# MULTIB.net
KiCad netlist of a schematic drawn in Altium Designer
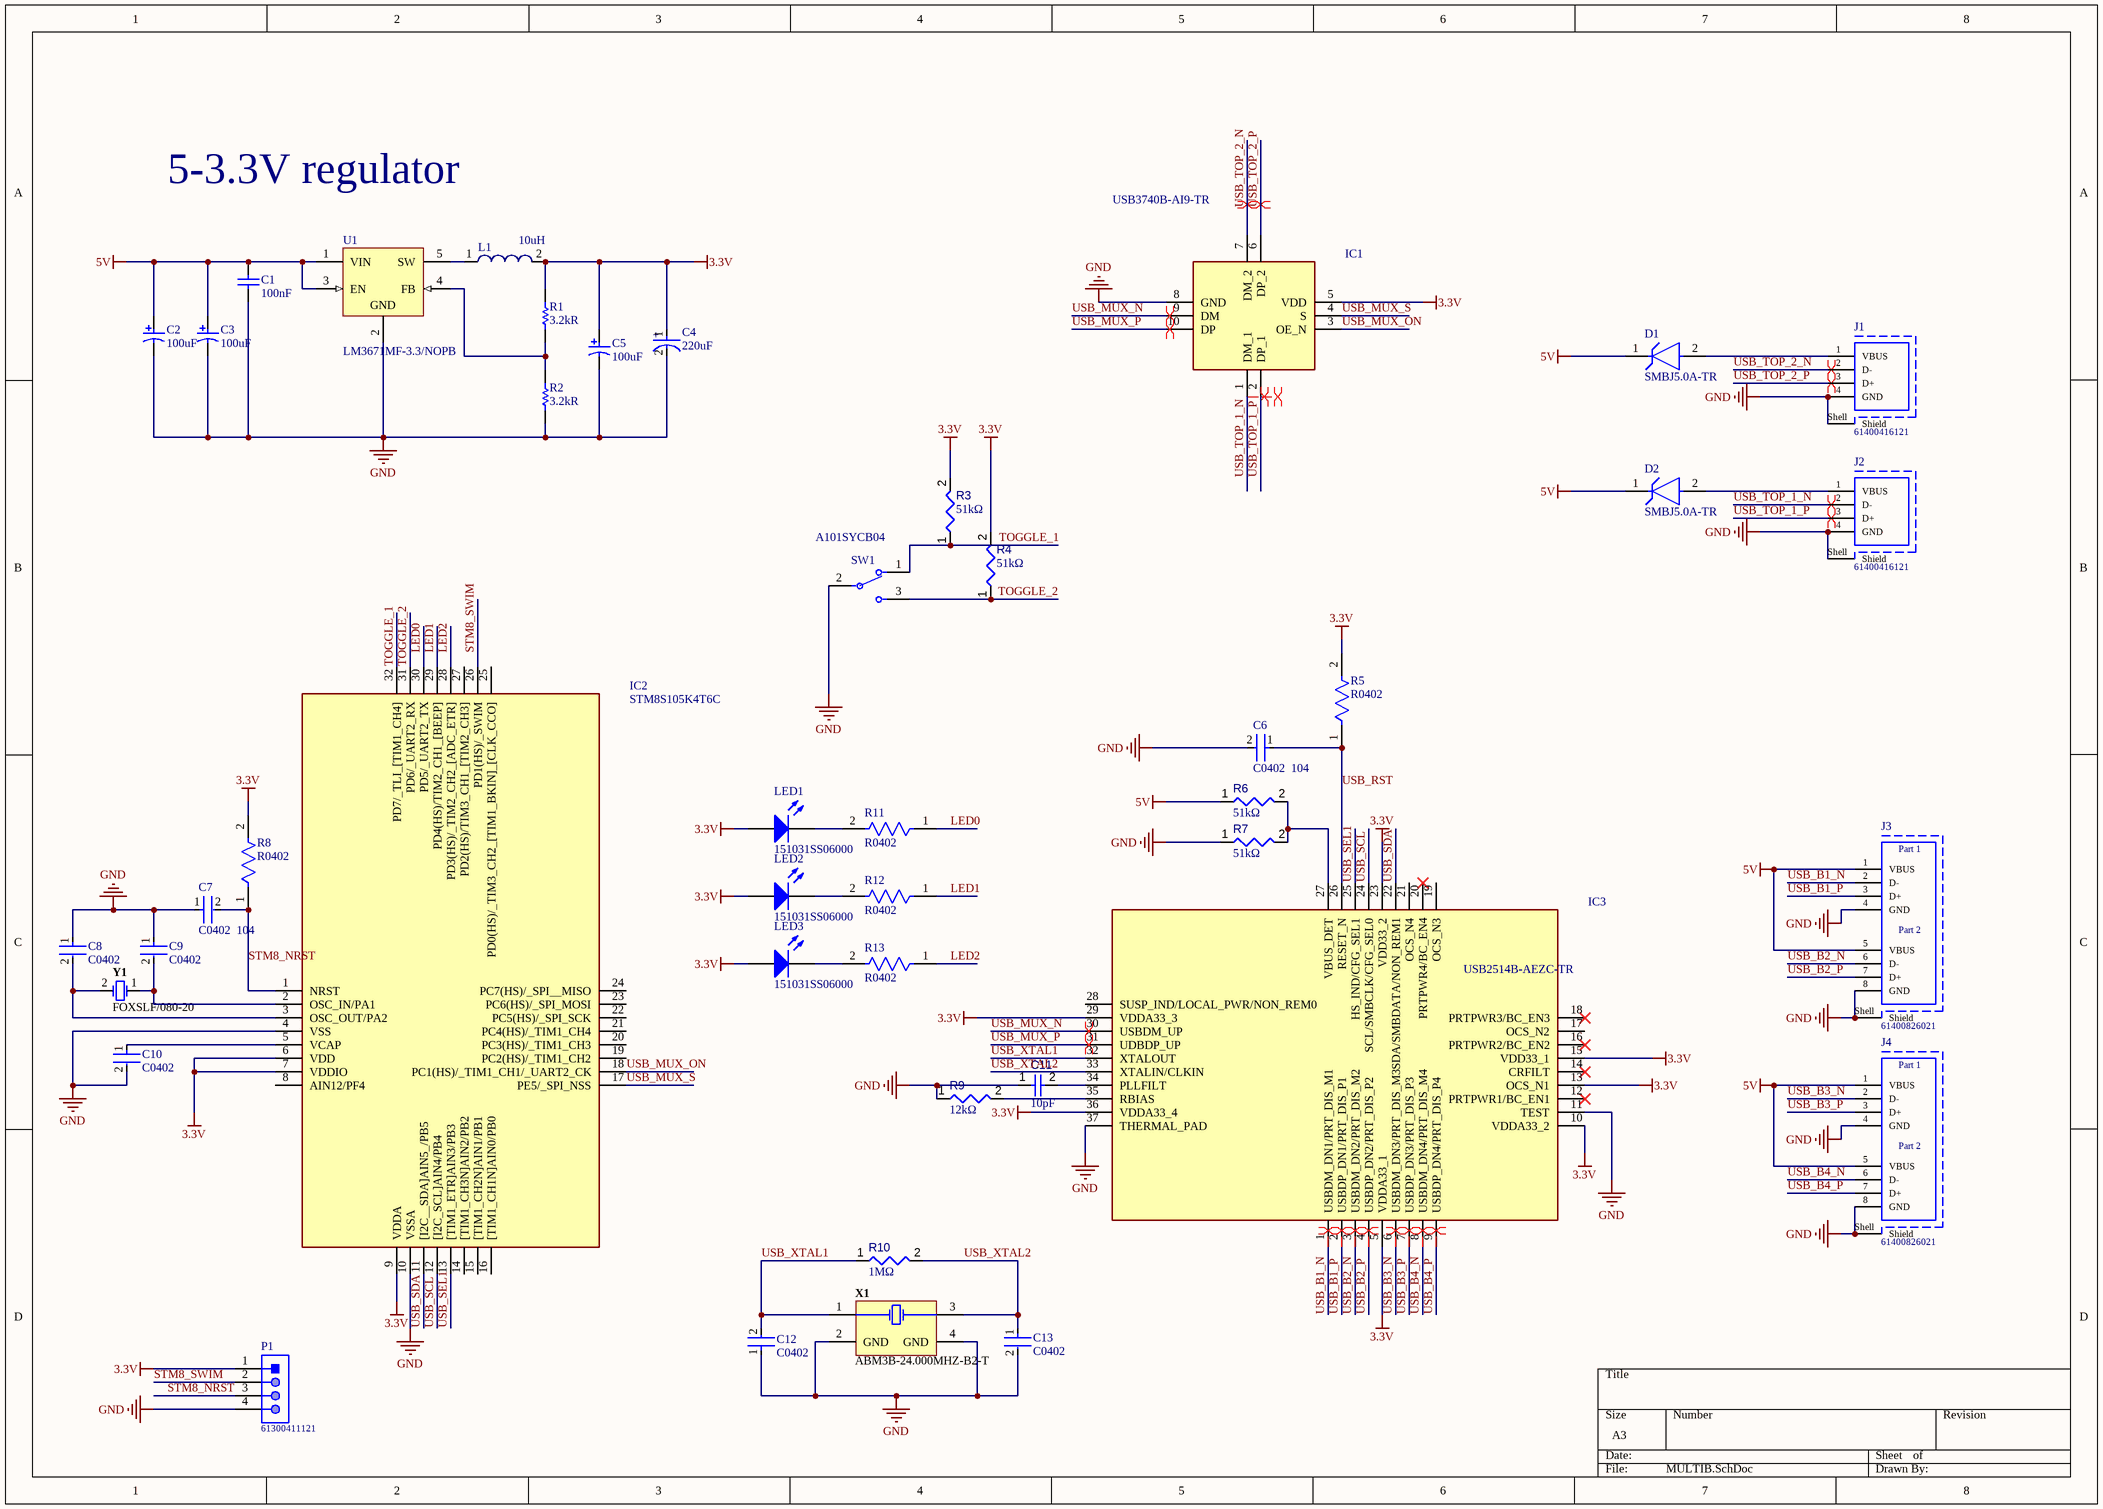
[diagram p0: MULTIB.SchDoc]

(export (version "E")
  (design (tool "Eeschema 10.0.6"))
  (components
    (comp (ref "C1")
      (value "100nF")
      (footprint "CAPC1608X90X35ML10T15")
      (description "Chip Capacitor, 22 pF, +/- 5%, 50 V, -55 to 125 degC, 0603 (1608 Metric), RoHS, Tape and Reel")
      (fields (field (name "MANUFACTURER") "Murata"))
      (libsource (lib "Altium Content Vault") (part "CAP-NP-2"))
    )
    (comp (ref "C2")
      (value "100uF")
      (footprint "CAPPR65-350-1150X800X1250")
      (description "Aluminum Electrolytic Capacitor, 100 uF, +/- 20%, 50 V, -40 to 85 degC, 2-Pin THD, RoHS, Bulk")
      (fields (field (name "MANUFACTURER") "Panasonic") (field (name "VOLTAGE") "50V"))
      (libsource (lib "Altium Content Vault") (part "CAP-P-2"))
    )
    (comp (ref "C3")
      (value "100uF")
      (footprint "CAPPR65-350-1150X800X1250")
      (description "Aluminum Electrolytic Capacitor, 100 uF, +/- 20%, 50 V, -40 to 85 degC, 2-Pin THD, RoHS, Bulk")
      (fields (field (name "MANUFACTURER") "Panasonic") (field (name "VOLTAGE") "50V"))
      (libsource (lib "Altium Content Vault") (part "CAP-P-2"))
    )
    (comp (ref "C4")
      (value "220uF")
      (footprint "FP-EEU-FC1V221L-MFG")
      (description "CAP ALUM 220UF 20% 35V RADIAL")
      (fields
        (field (name "OCTOPART") "https://octopart.com/eeu-fc1v221l-panasonic-39478519")
        (field (name "MANUFACTURER") "Panasonic Electronic Components")
      )
      (libsource (lib "Altium Content Vault") (part "385ce6c70a3ab0aa1e866f00bd8ed49"))
    )
    (comp (ref "C5")
      (value "100uF")
      (footprint "CAPPR65-350-1150X800X1250")
      (description "Aluminum Electrolytic Capacitor, 100 uF, +/- 20%, 50 V, -40 to 85 degC, 2-Pin THD, RoHS, Bulk")
      (fields (field (name "MANUFACTURER") "Panasonic") (field (name "VOLTAGE") "50V"))
      (libsource (lib "Altium Content Vault") (part "CAP-P-2"))
    )
    (comp (ref "C6")
      (value "C0402  104")
      (footprint "FP-C0402-BB-MFG")
      (description "CAP CER 0.1UF 10V X5R 0402")
      (fields (field (name "MANUFACTURER") "Kemet") (field (name "TOLERANCE") "0.1"))
      (libsource (lib "Altium Content Vault") (part "b4654b650e69147ec39a6b967a45e02"))
    )
    (comp (ref "C7")
      (value "C0402  104")
      (footprint "FP-C0402-BB-MFG")
      (description "CAP CER 0.1UF 10V X5R 0402")
      (fields (field (name "MANUFACTURER") "Kemet") (field (name "TOLERANCE") "0.1"))
      (libsource (lib "Altium Content Vault") (part "b4654b650e69147ec39a6b967a45e02"))
    )
    (comp (ref "C8")
      (value "C0402")
      (footprint "FP-C0402-BB-MFG")
      (description "CAP CER 0.1UF 10V X5R 0402")
      (fields (field (name "MANUFACTURER") "Kemet") (field (name "TOLERANCE") "0.1"))
      (libsource (lib "Altium Content Vault") (part "b4654b650e69147ec39a6b967a45e02"))
    )
    (comp (ref "C9")
      (value "C0402")
      (footprint "FP-C0402-BB-MFG")
      (description "CAP CER 0.1UF 10V X5R 0402")
      (fields (field (name "MANUFACTURER") "Kemet") (field (name "TOLERANCE") "0.1"))
      (libsource (lib "Altium Content Vault") (part "b4654b650e69147ec39a6b967a45e02"))
    )
    (comp (ref "C10")
      (value "C0402")
      (footprint "FP-C0402-BB-MFG")
      (description "CAP CER 0.1UF 10V X5R 0402")
      (fields (field (name "MANUFACTURER") "Kemet") (field (name "TOLERANCE") "0.1"))
      (libsource (lib "Altium Content Vault") (part "b4654b650e69147ec39a6b967a45e02"))
    )
    (comp (ref "C11")
      (value "10pF")
      (footprint "CAPC1608X90X40ML10T20")
      (description "Chip Capacitor, 10 pF, +/- 5%, 50 V, 0603 (1608 Metric)")
      (fields (field (name "TOLERANCE") "5%") (field (name "Comment") "Capacitor 10 pF +/- 5% 50 V 0603"))
      (libsource (lib "Jacky Yuen") (part "CAP-NP-2"))
    )
    (comp (ref "C12")
      (value "C0402")
      (footprint "FP-C0402-BB-MFG")
      (description "CAP CER 0.1UF 10V X5R 0402")
      (fields (field (name "MANUFACTURER") "Kemet") (field (name "TOLERANCE") "0.1"))
      (libsource (lib "Altium Content Vault") (part "b4654b650e69147ec39a6b967a45e02"))
    )
    (comp (ref "C13")
      (value "C0402")
      (footprint "FP-C0402-BB-MFG")
      (description "CAP CER 0.1UF 10V X5R 0402")
      (fields (field (name "MANUFACTURER") "Kemet") (field (name "TOLERANCE") "0.1"))
      (libsource (lib "Altium Content Vault") (part "b4654b650e69147ec39a6b967a45e02"))
    )
    (comp (ref "D1")
      (value "SMBJ5.0A-TR")
      (footprint "FP-SMB-MFG")
      (description "TVS DIODE 5V 13.4V SMB")
      (fields
        (field (name "MANUFACTURER") "STMicroelectronics")
        (field (name "OCTOPART") "https://octopart.com/smbj5.0a-tr-stmicroelectronics-347079")
      )
      (libsource (lib "Altium Content Vault") (part "7ddec9f632b8482e96f7745d0fbdf39"))
    )
    (comp (ref "D2")
      (value "SMBJ5.0A-TR")
      (footprint "FP-SMB-MFG")
      (description "TVS DIODE 5V 13.4V SMB")
      (fields
        (field (name "MANUFACTURER") "STMicroelectronics")
        (field (name "OCTOPART") "https://octopart.com/smbj5.0a-tr-stmicroelectronics-347079")
      )
      (libsource (lib "Altium Content Vault") (part "7ddec9f632b8482e96f7745d0fbdf39"))
    )
    (comp (ref "IC1")
      (value "USB3740B-AI9-TR")
      (footprint "SamacSys:USB3740BAI9TR")
      (description "Integrated Circuit")
      (fields (field (name "MOUSER PART NUMBER") "886-USB3740B-AI9-TR"))
      (libsource (lib "*") (part "USB3740B-AI9-TR"))
    )
    (comp (ref "IC2")
      (value "STM8S105K4T6C")
      (footprint "SamacSys:QFP80P900X900X160-32N")
      (description "Integrated Circuit")
      (fields (field (name "MOUSER PART NUMBER") "511-STM8S105K4T6C"))
      (libsource (lib "*") (part "STM8S105K4T6C"))
    )
    (comp (ref "IC3")
      (value "USB2514B-AEZC-TR")
      (footprint "SamacSys:QFN50P600X600X100-37N-D")
      (description "Integrated Circuit")
      (fields (field (name "MOUSER PART NUMBER") "886-USB2514B-AEZC-TR"))
      (libsource (lib "*") (part "USB2514B-AEZC-TR"))
    )
    (comp (ref "J1")
      (value "61400416121")
      (footprint "61400416121")
      (description "USB 2.0 Type B Receptacle WR-COM, Horizontal, THT, with Pads and Pegs")
      (fields (field (name "MANUFACTURER") "Wurth Elektronik") (field (name "PUBLISHER") "WurthElektronik"))
      (libsource (lib "Altium Content Vault") (part "WE-USB-4-1SHLD"))
    )
    (comp (ref "J2")
      (value "61400416121")
      (footprint "61400416121")
      (description "USB 2.0 Type B Receptacle WR-COM, Horizontal, THT, with Pads and Pegs")
      (fields (field (name "MANUFACTURER") "Wurth Elektronik") (field (name "PUBLISHER") "WurthElektronik"))
      (libsource (lib "Altium Content Vault") (part "WE-USB-4-1SHLD"))
    )
    (comp (ref "J3")
      (value "61400826021")
      (footprint "61400826021")
      (description "USB 2.0 Type A Receptacle WR-COM, Stacked Horizontal, THT")
      (fields (field (name "MANUFACTURER") "Wurth Elektronik") (field (name "PUBLISHER") "WurthElektronik"))
      (libsource (lib "Altium Content Vault") (part "WE-USB-8-1SHLD"))
    )
    (comp (ref "J4")
      (value "61400826021")
      (footprint "61400826021")
      (description "USB 2.0 Type A Receptacle WR-COM, Stacked Horizontal, THT")
      (fields (field (name "MANUFACTURER") "Wurth Elektronik") (field (name "PUBLISHER") "WurthElektronik"))
      (libsource (lib "Altium Content Vault") (part "WE-USB-8-1SHLD"))
    )
    (comp (ref "L1")
      (value "10uH")
      (footprint "WE-SPC 4838")
      (description "SMD Shielded Power Inductor WE-SPC, L=10 µH")
      (fields (field (name "MANUFACTURER") "Wuerth Elektronik") (field (name "PARTNUMBER") "74408943100"))
      (libsource (lib "Altium Content Vault") (part "WE-IND-INDUCTOR-2"))
    )
    (comp (ref "LED1")
      (value "151031SS06000")
      (footprint "Type 3mm")
      (description "THT LED round mono-color color lens, WL-TMRW, Super Red")
      (fields (field (name "MANUFACTURER") "Wuerth Elektronik"))
      (libsource (lib "Altium Content Vault") (part "WE-LED_K1A2-2"))
    )
    (comp (ref "LED2")
      (value "151031SS06000")
      (footprint "Type 3mm")
      (description "THT LED round mono-color color lens, WL-TMRW, Super Red")
      (fields (field (name "MANUFACTURER") "Wuerth Elektronik"))
      (libsource (lib "Altium Content Vault") (part "WE-LED_K1A2-2"))
    )
    (comp (ref "LED3")
      (value "151031SS06000")
      (footprint "Type 3mm")
      (description "THT LED round mono-color color lens, WL-TMRW, Super Red")
      (fields (field (name "MANUFACTURER") "Wuerth Elektronik"))
      (libsource (lib "Altium Content Vault") (part "WE-LED_K1A2-2"))
    )
    (comp (ref "P1")
      (value "61300411121")
      (footprint "61300411121")
      (description "THT Vertical Pin Header WR-PHD, Pitch 2.54 mm, Single Row, 4 pins")
      (fields (field (name "MANUFACTURER") "Wurth Elektronik") (field (name "PUBLISHER") "WurthElektronik"))
      (libsource (lib "Altium Content Vault") (part "WE-CN-1P-M-R4"))
    )
    (comp (ref "R1")
      (value "3.2kR")
      (footprint "RESC1005X40X25LL05T05")
      (description "Chip Resistor, 4.7 KOhm, +/- 1%, 0.1 W, -55 to 155 degC, 0402 (1005 Metric), RoHS, Tape and Reel")
      (fields (field (name "TOLERANCE") "1%") (field (name "PARTNUMBER") "ERJ-2RKF4701X"))
      (libsource (lib "Altium Content Vault") (part "RES-2"))
    )
    (comp (ref "R2")
      (value "3.2kR")
      (footprint "RESC1005X40X25LL05T05")
      (description "Chip Resistor, 4.7 KOhm, +/- 1%, 0.1 W, -55 to 155 degC, 0402 (1005 Metric), RoHS, Tape and Reel")
      (fields (field (name "TOLERANCE") "1%") (field (name "PARTNUMBER") "ERJ-2RKF4701X"))
      (libsource (lib "Altium Content Vault") (part "RES-2"))
    )
    (comp (ref "R3")
      (value "51kΩ")
      (footprint "RESC0603(1608)_L")
      (description "120R 0.1W 5% 0603 (1608 Metric)  SMD")
      (fields (field (name "POWER") "0.1W") (field (name "TOLERANCE") "5%"))
      (libsource (lib "Jacky Yuen") (part "120R3J"))
    )
    (comp (ref "R4")
      (value "51kΩ")
      (footprint "RESC0603(1608)_L")
      (description "120R 0.1W 5% 0603 (1608 Metric)  SMD")
      (fields (field (name "POWER") "0.1W") (field (name "TOLERANCE") "5%"))
      (libsource (lib "Jacky Yuen") (part "120R3J"))
    )
    (comp (ref "R5")
      (value "R0402")
      (footprint "FP-CRCW0402-e3-IPC_C")
      (description "RES Thick Film, 32.4kΩ, 1%, 0.063W, 100ppm/°C, 0402")
      (fields (field (name "TOLERANCE") "1%"))
      (libsource (lib "Altium Content Vault") (part "1029c3af85768c4190bb7ad29bc67b5"))
    )
    (comp (ref "R6")
      (value "51kΩ")
      (footprint "RESC0603(1608)_L")
      (description "120R 0.1W 5% 0603 (1608 Metric)  SMD")
      (fields (field (name "POWER") "0.1W") (field (name "TOLERANCE") "5%"))
      (libsource (lib "Jacky Yuen") (part "120R3J"))
    )
    (comp (ref "R7")
      (value "51kΩ")
      (footprint "RESC0603(1608)_L")
      (description "120R 0.1W 5% 0603 (1608 Metric)  SMD")
      (fields (field (name "POWER") "0.1W") (field (name "TOLERANCE") "5%"))
      (libsource (lib "Jacky Yuen") (part "120R3J"))
    )
    (comp (ref "R8")
      (value "R0402")
      (footprint "FP-CRCW0402-e3-IPC_C")
      (description "RES Thick Film, 32.4kΩ, 1%, 0.063W, 100ppm/°C, 0402")
      (fields (field (name "TOLERANCE") "1%"))
      (libsource (lib "Altium Content Vault") (part "1029c3af85768c4190bb7ad29bc67b5"))
    )
    (comp (ref "R9")
      (value "12kΩ")
      (footprint "RESC0603(1608)_L")
      (description "120R 0.1W 5% 0603 (1608 Metric)  SMD")
      (fields (field (name "POWER") "0.1W") (field (name "TOLERANCE") "5%"))
      (libsource (lib "Jacky Yuen") (part "120R3J"))
    )
    (comp (ref "R10")
      (value "1MΩ")
      (footprint "RESC0603(1608)_L")
      (description "120R 0.1W 5% 0603 (1608 Metric)  SMD")
      (fields (field (name "POWER") "0.1W") (field (name "TOLERANCE") "5%"))
      (libsource (lib "Jacky Yuen") (part "120R3J"))
    )
    (comp (ref "R11")
      (value "R0402")
      (footprint "FP-CRCW0402-e3-IPC_C")
      (description "RES Thick Film, 32.4kΩ, 1%, 0.063W, 100ppm/°C, 0402")
      (fields (field (name "TOLERANCE") "1%"))
      (libsource (lib "Altium Content Vault") (part "1029c3af85768c4190bb7ad29bc67b5"))
    )
    (comp (ref "R12")
      (value "R0402")
      (footprint "FP-CRCW0402-e3-IPC_C")
      (description "RES Thick Film, 32.4kΩ, 1%, 0.063W, 100ppm/°C, 0402")
      (fields (field (name "TOLERANCE") "1%"))
      (libsource (lib "Altium Content Vault") (part "1029c3af85768c4190bb7ad29bc67b5"))
    )
    (comp (ref "R13")
      (value "R0402")
      (footprint "FP-CRCW0402-e3-IPC_C")
      (description "RES Thick Film, 32.4kΩ, 1%, 0.063W, 100ppm/°C, 0402")
      (fields (field (name "TOLERANCE") "1%"))
      (libsource (lib "Altium Content Vault") (part "1029c3af85768c4190bb7ad29bc67b5"))
    )
    (comp (ref "SW1")
      (value "A101SYCB04")
      (footprint "FP-A101SYCB04-MFG")
      (description "SWITCH TOGGLE SPDT 0.4VA 20V")
      (libsource (lib "Altium Content Vault") (part "52c419afdc2a387c7d548259a9aeefb"))
    )
    (comp (ref "U1")
      (value "LM3671MF-3.3/NOPB")
      (footprint "DBV0005A_N")
      (description "2MHz, 600mA Step-Down DC-DC Converter, 5-pin SOT-23, Pb-Free")
      (fields (field (name "MANUFACTURER") "Texas Instruments"))
      (libsource (lib "Altium Content Vault") (part "PM-DCDC-LM3670-5"))
    )
    (comp (ref "X1")
      (value "ABM3B-24.000MHZ-B2-T")
      (footprint "ABRA-ABM3B-4_V")
      (description "Ceramic SMD Crystal, 24 MHz, +/- 20 ppm, 50 Ohm, -20 to 70 degC, 4-Pin SMD, RoHS, Tape and Reel")
      (libsource (lib "Altium Content Vault") (part "XTAL-1-3-4"))
    )
    (comp (ref "Y1")
      (value "FOXSLF/080-20")
      (footprint "FOX-FOXSLF080-20")
      (description "Resistance Weld Thru-Hole Crystal, 8 MHz, -20 to 70 degC, 2-Pin THD, RoHS, Bulk")
      (libsource (lib "Altium Content Vault") (part "XTAL-1-2-2"))
    )
  )
  (nets
    (net (code "1") (name "/LED0") (class "Default")
      (node (ref "IC2") (pin "30") (pinfunction "PD5/_UART2_TX_30") (pintype "passive"))
      (node (ref "R11") (pin "1") (pinfunction "1_1") (pintype "passive"))
    )
    (net (code "2") (name "/LED1") (class "Default")
      (node (ref "IC2") (pin "29") (pinfunction "PD4(HS)/TIM2_CH1_[BEEP]_29") (pintype "passive"))
      (node (ref "R12") (pin "1") (pinfunction "1_1") (pintype "passive"))
    )
    (net (code "3") (name "/LED2") (class "Default")
      (node (ref "IC2") (pin "28") (pinfunction "PD3(HS)/_TIM2_CH2_[ADC_ETR]_28") (pintype "passive"))
      (node (ref "R13") (pin "1") (pinfunction "1_1") (pintype "passive"))
    )
    (net (code "4") (name "/STM8_NRST") (class "Default")
      (node (ref "C7") (pin "2") (pinfunction "2_2") (pintype "passive"))
      (node (ref "IC2") (pin "1") (pinfunction "NRST_1") (pintype "passive"))
      (node (ref "P1") (pin "3") (pinfunction "3_3") (pintype "passive"))
      (node (ref "R8") (pin "1") (pinfunction "1_1") (pintype "passive"))
    )
    (net (code "5") (name "/STM8_SWIM") (class "Default")
      (node (ref "IC2") (pin "26") (pinfunction "PD1(HS)/_SWIM_26") (pintype "passive"))
      (node (ref "P1") (pin "2") (pinfunction "2_2") (pintype "passive"))
    )
    (net (code "6") (name "/TOGGLE_1") (class "Default")
      (node (ref "IC2") (pin "32") (pinfunction "PD7/_TLI_[TIM1_CH4]_32") (pintype "passive"))
      (node (ref "R3") (pin "1") (pinfunction "1_1") (pintype "passive"))
      (node (ref "SW1") (pin "1") (pinfunction "1_1") (pintype "passive"))
    )
    (net (code "7") (name "/TOGGLE_2") (class "Default")
      (node (ref "IC2") (pin "31") (pinfunction "PD6/_UART2_RX_31") (pintype "passive"))
      (node (ref "R4") (pin "1") (pinfunction "1_1") (pintype "passive"))
      (node (ref "SW1") (pin "3") (pinfunction "3_3") (pintype "passive"))
    )
    (net (code "8") (name "/USB_B1_N") (class "Default")
      (node (ref "IC3") (pin "1") (pinfunction "USBDM_DN1/PRT_DIS_M1_1") (pintype "passive"))
      (node (ref "J3") (pin "2") (pinfunction "D-_2") (pintype "passive"))
    )
    (net (code "9") (name "/USB_B1_P") (class "Default")
      (node (ref "IC3") (pin "2") (pinfunction "USBDP_DN1/PRT_DIS_P1_2") (pintype "passive"))
      (node (ref "J3") (pin "3") (pinfunction "D+_3") (pintype "passive"))
    )
    (net (code "10") (name "/USB_B2_N") (class "Default")
      (node (ref "IC3") (pin "3") (pinfunction "USBDM_DN2/PRT_DIS_M2_3") (pintype "passive"))
      (node (ref "J3") (pin "6") (pinfunction "D-_6") (pintype "passive"))
    )
    (net (code "11") (name "/USB_B2_P") (class "Default")
      (node (ref "IC3") (pin "4") (pinfunction "USBDP_DN2/PRT_DIS_P2_4") (pintype "passive"))
      (node (ref "J3") (pin "7") (pinfunction "D+_7") (pintype "passive"))
    )
    (net (code "12") (name "/USB_B3_N") (class "Default")
      (node (ref "IC3") (pin "6") (pinfunction "USBDM_DN3/PRT_DIS_M3_6") (pintype "passive"))
      (node (ref "J4") (pin "2") (pinfunction "D-_2") (pintype "passive"))
    )
    (net (code "13") (name "/USB_B3_P") (class "Default")
      (node (ref "IC3") (pin "7") (pinfunction "USBDP_DN3/PRT_DIS_P3_7") (pintype "passive"))
      (node (ref "J4") (pin "3") (pinfunction "D+_3") (pintype "passive"))
    )
    (net (code "14") (name "/USB_B4_N") (class "Default")
      (node (ref "IC3") (pin "8") (pinfunction "USBDM_DN4/PRT_DIS_M4_8") (pintype "passive"))
      (node (ref "J4") (pin "6") (pinfunction "D-_6") (pintype "passive"))
    )
    (net (code "15") (name "/USB_B4_P") (class "Default")
      (node (ref "IC3") (pin "9") (pinfunction "USBDP_DN4/PRT_DIS_P4_9") (pintype "passive"))
      (node (ref "J4") (pin "7") (pinfunction "D+_7") (pintype "passive"))
    )
    (net (code "16") (name "/USB_MUX_N") (class "Default")
      (node (ref "IC1") (pin "9") (pinfunction "DM_9") (pintype "passive"))
      (node (ref "IC3") (pin "30") (pinfunction "USBDM_UP_30") (pintype "passive"))
    )
    (net (code "17") (name "/USB_MUX_ON") (class "Default")
      (node (ref "IC1") (pin "3") (pinfunction "OE_N_3") (pintype "passive"))
      (node (ref "IC2") (pin "18") (pinfunction "PC1(HS)/_TIM1_CH1/_UART2_CK_18") (pintype "passive"))
    )
    (net (code "18") (name "/USB_MUX_P") (class "Default")
      (node (ref "IC1") (pin "10") (pinfunction "DP_10") (pintype "passive"))
      (node (ref "IC3") (pin "31") (pinfunction "UDBDP_UP_31") (pintype "passive"))
    )
    (net (code "19") (name "/USB_MUX_S") (class "Default")
      (node (ref "IC1") (pin "4") (pinfunction "S_4") (pintype "passive"))
      (node (ref "IC2") (pin "17") (pinfunction "PE5/_SPI_NSS_17") (pintype "passive"))
    )
    (net (code "20") (name "/USB_RST") (class "Default")
      (node (ref "C6") (pin "1") (pinfunction "1_1") (pintype "passive"))
      (node (ref "IC3") (pin "26") (pinfunction "RESET_N_26") (pintype "passive"))
      (node (ref "R5") (pin "1") (pinfunction "1_1") (pintype "passive"))
    )
    (net (code "21") (name "/USB_SCL") (class "Default")
      (node (ref "IC2") (pin "12") (pinfunction "[I2C_SCL]AIN4/PB4_12") (pintype "passive"))
      (node (ref "IC3") (pin "24") (pinfunction "SCL/SMBCLK/CFG_SEL0_24") (pintype "passive"))
    )
    (net (code "22") (name "/USB_SDA") (class "Default")
      (node (ref "IC2") (pin "11") (pinfunction "[I2C__SDA]AIN5_/PB5_11") (pintype "passive"))
      (node (ref "IC3") (pin "22") (pinfunction "SDA/SMBDATA/NON_REM1_22") (pintype "passive"))
    )
    (net (code "23") (name "/USB_SEL1") (class "Default")
      (node (ref "IC2") (pin "13") (pinfunction "[TIM1_ETR]AIN3/PB3_13") (pintype "passive"))
      (node (ref "IC3") (pin "25") (pinfunction "HS_IND/CFG_SEL1_25") (pintype "passive"))
    )
    (net (code "24") (name "/USB_TOP_1_N") (class "Default")
      (node (ref "IC1") (pin "1") (pinfunction "DM_1_1") (pintype "passive"))
      (node (ref "J2") (pin "2") (pinfunction "D-_2") (pintype "passive"))
    )
    (net (code "25") (name "/USB_TOP_1_P") (class "Default")
      (node (ref "IC1") (pin "2") (pinfunction "DP_1_2") (pintype "passive"))
      (node (ref "J2") (pin "3") (pinfunction "D+_3") (pintype "passive"))
    )
    (net (code "26") (name "/USB_TOP_2_N") (class "Default")
      (node (ref "IC1") (pin "7") (pinfunction "DM_2_7") (pintype "passive"))
      (node (ref "J1") (pin "2") (pinfunction "D-_2") (pintype "passive"))
    )
    (net (code "27") (name "/USB_TOP_2_P") (class "Default")
      (node (ref "IC1") (pin "6") (pinfunction "DP_2_6") (pintype "passive"))
      (node (ref "J1") (pin "3") (pinfunction "D+_3") (pintype "passive"))
    )
    (net (code "28") (name "/USB_XTAL1") (class "Default")
      (node (ref "C12") (pin "2") (pinfunction "2_2") (pintype "passive"))
      (node (ref "IC3") (pin "32") (pinfunction "XTALOUT_32") (pintype "passive"))
      (node (ref "R10") (pin "1") (pinfunction "1_1") (pintype "passive"))
      (node (ref "X1") (pin "1") (pinfunction "X1_1") (pintype "passive"))
    )
    (net (code "29") (name "/USB_XTAL2") (class "Default")
      (node (ref "C13") (pin "1") (pinfunction "1_1") (pintype "passive"))
      (node (ref "IC3") (pin "33") (pinfunction "XTALIN/CLKIN_33") (pintype "passive"))
      (node (ref "R10") (pin "2") (pinfunction "2_2") (pintype "passive"))
      (node (ref "X1") (pin "3") (pinfunction "X2_3") (pintype "passive"))
    )
    (net (code "30") (name "3.3V") (class "Default")
      (node (ref "C4") (pin "1") (pinfunction "C_1") (pintype "passive"))
      (node (ref "C5") (pin "1") (pinfunction "1_1") (pintype "passive"))
      (node (ref "IC1") (pin "5") (pinfunction "VDD_5") (pintype "passive"))
      (node (ref "IC2") (pin "6") (pinfunction "VDD_6") (pintype "passive"))
      (node (ref "IC2") (pin "7") (pinfunction "VDDIO_7") (pintype "passive"))
      (node (ref "IC2") (pin "9") (pinfunction "VDDA_9") (pintype "passive"))
      (node (ref "IC3") (pin "10") (pinfunction "VDDA33_2_10") (pintype "passive"))
      (node (ref "IC3") (pin "13") (pinfunction "OCS_N1_13") (pintype "passive"))
      (node (ref "IC3") (pin "15") (pinfunction "VDD33_1_15") (pintype "passive"))
      (node (ref "IC3") (pin "23") (pinfunction "VDD33_2_23") (pintype "passive"))
      (node (ref "IC3") (pin "29") (pinfunction "VDDA33_3_29") (pintype "passive"))
      (node (ref "IC3") (pin "36") (pinfunction "VDDA33_4_36") (pintype "passive"))
      (node (ref "IC3") (pin "5") (pinfunction "VDDA33_1_5") (pintype "passive"))
      (node (ref "L1") (pin "2") (pinfunction "2_2") (pintype "passive"))
      (node (ref "LED1") (pin "2") (pinfunction "A_2") (pintype "passive"))
      (node (ref "LED2") (pin "2") (pinfunction "A_2") (pintype "passive"))
      (node (ref "LED3") (pin "2") (pinfunction "A_2") (pintype "passive"))
      (node (ref "P1") (pin "1") (pinfunction "1_1") (pintype "passive"))
      (node (ref "R1") (pin "2") (pinfunction "2_2") (pintype "passive"))
      (node (ref "R3") (pin "2") (pinfunction "2_2") (pintype "passive"))
      (node (ref "R4") (pin "2") (pinfunction "2_2") (pintype "passive"))
      (node (ref "R5") (pin "2") (pinfunction "2_2") (pintype "passive"))
      (node (ref "R8") (pin "2") (pinfunction "2_2") (pintype "passive"))
    )
    (net (code "31") (name "5V") (class "Default")
      (node (ref "C1") (pin "2") (pinfunction "2_2") (pintype "passive"))
      (node (ref "C2") (pin "1") (pinfunction "1_1") (pintype "passive"))
      (node (ref "C3") (pin "1") (pinfunction "1_1") (pintype "passive"))
      (node (ref "D1") (pin "1") (pinfunction "K_1") (pintype "passive"))
      (node (ref "D2") (pin "1") (pinfunction "K_1") (pintype "passive"))
      (node (ref "J3") (pin "1") (pinfunction "VBUS_1") (pintype "passive"))
      (node (ref "J3") (pin "5") (pinfunction "VBUS_5") (pintype "passive"))
      (node (ref "J4") (pin "1") (pinfunction "VBUS_1") (pintype "passive"))
      (node (ref "J4") (pin "5") (pinfunction "VBUS_5") (pintype "passive"))
      (node (ref "R6") (pin "1") (pinfunction "1_1") (pintype "passive"))
      (node (ref "U1") (pin "1") (pinfunction "VIN_1") (pintype "power_in"))
      (node (ref "U1") (pin "3") (pinfunction "EN_3") (pintype "input"))
    )
    (net (code "32") (name "GND") (class "Default")
      (node (ref "C1") (pin "1") (pinfunction "1_1") (pintype "passive"))
      (node (ref "C10") (pin "2") (pinfunction "2_2") (pintype "passive"))
      (node (ref "C11") (pin "1") (pinfunction "1_1") (pintype "passive"))
      (node (ref "C12") (pin "1") (pinfunction "1_1") (pintype "passive"))
      (node (ref "C13") (pin "2") (pinfunction "2_2") (pintype "passive"))
      (node (ref "C2") (pin "2") (pinfunction "2_2") (pintype "passive"))
      (node (ref "C3") (pin "2") (pinfunction "2_2") (pintype "passive"))
      (node (ref "C4") (pin "2") (pinfunction "A_2") (pintype "passive"))
      (node (ref "C5") (pin "2") (pinfunction "2_2") (pintype "passive"))
      (node (ref "C6") (pin "2") (pinfunction "2_2") (pintype "passive"))
      (node (ref "C7") (pin "1") (pinfunction "1_1") (pintype "passive"))
      (node (ref "C8") (pin "1") (pinfunction "1_1") (pintype "passive"))
      (node (ref "C9") (pin "1") (pinfunction "1_1") (pintype "passive"))
      (node (ref "IC1") (pin "8") (pinfunction "GND_8") (pintype "passive"))
      (node (ref "IC2") (pin "10") (pinfunction "VSSA_10") (pintype "passive"))
      (node (ref "IC2") (pin "4") (pinfunction "VSS_4") (pintype "passive"))
      (node (ref "IC3") (pin "11") (pinfunction "TEST_11") (pintype "passive"))
      (node (ref "IC3") (pin "37") (pinfunction "THERMAL_PAD_37") (pintype "passive"))
      (node (ref "J1") (pin "4") (pinfunction "GND_4") (pintype "passive"))
      (node (ref "J1") (pin "Shell") (pinfunction "Shield_Shell") (pintype "passive"))
      (node (ref "J2") (pin "4") (pinfunction "GND_4") (pintype "passive"))
      (node (ref "J2") (pin "Shell") (pinfunction "Shield_Shell") (pintype "passive"))
      (node (ref "J3") (pin "4") (pinfunction "GND_4") (pintype "passive"))
      (node (ref "J3") (pin "8") (pinfunction "GND_8") (pintype "passive"))
      (node (ref "J3") (pin "Shell") (pinfunction "Shield_Shell") (pintype "passive"))
      (node (ref "J4") (pin "4") (pinfunction "GND_4") (pintype "passive"))
      (node (ref "J4") (pin "8") (pinfunction "GND_8") (pintype "passive"))
      (node (ref "J4") (pin "Shell") (pinfunction "Shield_Shell") (pintype "passive"))
      (node (ref "P1") (pin "4") (pinfunction "4_4") (pintype "passive"))
      (node (ref "R2") (pin "1") (pinfunction "1_1") (pintype "passive"))
      (node (ref "R7") (pin "1") (pinfunction "1_1") (pintype "passive"))
      (node (ref "R9") (pin "1") (pinfunction "1_1") (pintype "passive"))
      (node (ref "SW1") (pin "2") (pinfunction "2_2") (pintype "passive"))
      (node (ref "U1") (pin "2") (pinfunction "GND_2") (pintype "power_in"))
      (node (ref "X1") (pin "2") (pinfunction "GND_2") (pintype "power_in"))
      (node (ref "X1") (pin "4") (pinfunction "GND_4") (pintype "power_in"))
    )
    (net (code "33") (name "Net-(D1-A)") (class "Default")
      (node (ref "D1") (pin "2") (pinfunction "A_2") (pintype "passive"))
      (node (ref "J1") (pin "1") (pinfunction "VBUS_1") (pintype "passive"))
    )
    (net (code "34") (name "Net-(D2-A)") (class "Default")
      (node (ref "D2") (pin "2") (pinfunction "A_2") (pintype "passive"))
      (node (ref "J2") (pin "1") (pinfunction "VBUS_1") (pintype "passive"))
    )
    (net (code "35") (name "Net-(IC2-OSC_IN{slash}PA1)") (class "Default")
      (node (ref "C9") (pin "2") (pinfunction "2_2") (pintype "passive"))
      (node (ref "IC2") (pin "2") (pinfunction "OSC_IN/PA1_2") (pintype "passive"))
      (node (ref "Y1") (pin "1") (pinfunction "1_1") (pintype "passive"))
    )
    (net (code "36") (name "Net-(IC2-OSC_OUT{slash}PA2)") (class "Default")
      (node (ref "C8") (pin "2") (pinfunction "2_2") (pintype "passive"))
      (node (ref "IC2") (pin "3") (pinfunction "OSC_OUT/PA2_3") (pintype "passive"))
      (node (ref "Y1") (pin "2") (pinfunction "2_2") (pintype "passive"))
    )
    (net (code "37") (name "Net-(IC2-VCAP)") (class "Default")
      (node (ref "C10") (pin "1") (pinfunction "1_1") (pintype "passive"))
      (node (ref "IC2") (pin "5") (pinfunction "VCAP_5") (pintype "passive"))
    )
    (net (code "38") (name "Net-(IC3-PLLFILT)") (class "Default")
      (node (ref "C11") (pin "2") (pinfunction "2_2") (pintype "passive"))
      (node (ref "IC3") (pin "34") (pinfunction "PLLFILT_34") (pintype "passive"))
    )
    (net (code "39") (name "Net-(IC3-RBIAS)") (class "Default")
      (node (ref "IC3") (pin "35") (pinfunction "RBIAS_35") (pintype "passive"))
      (node (ref "R9") (pin "2") (pinfunction "2_2") (pintype "passive"))
    )
    (net (code "40") (name "Net-(IC3-VBUS_DET)") (class "Default")
      (node (ref "IC3") (pin "27") (pinfunction "VBUS_DET_27") (pintype "passive"))
      (node (ref "R6") (pin "2") (pinfunction "2_2") (pintype "passive"))
      (node (ref "R7") (pin "2") (pinfunction "2_2") (pintype "passive"))
    )
    (net (code "41") (name "Net-(LED1-K)") (class "Default")
      (node (ref "LED1") (pin "1") (pinfunction "K_1") (pintype "passive"))
      (node (ref "R11") (pin "2") (pinfunction "2_2") (pintype "passive"))
    )
    (net (code "42") (name "Net-(LED2-K)") (class "Default")
      (node (ref "LED2") (pin "1") (pinfunction "K_1") (pintype "passive"))
      (node (ref "R12") (pin "2") (pinfunction "2_2") (pintype "passive"))
    )
    (net (code "43") (name "Net-(LED3-K)") (class "Default")
      (node (ref "LED3") (pin "1") (pinfunction "K_1") (pintype "passive"))
      (node (ref "R13") (pin "2") (pinfunction "2_2") (pintype "passive"))
    )
    (net (code "44") (name "Net-(U1-FB)") (class "Default")
      (node (ref "R1") (pin "1") (pinfunction "1_1") (pintype "passive"))
      (node (ref "R2") (pin "2") (pinfunction "2_2") (pintype "passive"))
      (node (ref "U1") (pin "4") (pinfunction "FB_4") (pintype "input"))
    )
    (net (code "45") (name "Net-(U1-SW)") (class "Default")
      (node (ref "L1") (pin "1") (pinfunction "1_1") (pintype "passive"))
      (node (ref "U1") (pin "5") (pinfunction "SW_5") (pintype "power_in"))
    )
    (net (code "46") (name "unconnected-(IC2-AIN12{slash}PF4-Pad8)") (class "Default")
      (node (ref "IC2") (pin "8") (pinfunction "AIN12/PF4_8") (pintype "passive"))
    )
    (net (code "47") (name "unconnected-(IC2-PC2(HS){slash}_TIM1_CH2-Pad19)") (class "Default")
      (node (ref "IC2") (pin "19") (pinfunction "PC2(HS)/_TIM1_CH2_19") (pintype "passive"))
    )
    (net (code "48") (name "unconnected-(IC2-PC3(HS){slash}_TIM1_CH3-Pad20)") (class "Default")
      (node (ref "IC2") (pin "20") (pinfunction "PC3(HS)/_TIM1_CH3_20") (pintype "passive"))
    )
    (net (code "49") (name "unconnected-(IC2-PC4(HS){slash}_TIM1_CH4-Pad21)") (class "Default")
      (node (ref "IC2") (pin "21") (pinfunction "PC4(HS)/_TIM1_CH4_21") (pintype "passive"))
    )
    (net (code "50") (name "unconnected-(IC2-PC5(HS){slash}_SPI_SCK-Pad22)") (class "Default")
      (node (ref "IC2") (pin "22") (pinfunction "PC5(HS)/_SPI_SCK_22") (pintype "passive"))
    )
    (net (code "51") (name "unconnected-(IC2-PC6(HS){slash}_SPI_MOSI-Pad23)") (class "Default")
      (node (ref "IC2") (pin "23") (pinfunction "PC6(HS)/_SPI_MOSI_23") (pintype "passive"))
    )
    (net (code "52") (name "unconnected-(IC2-PC7(HS){slash}_SPI__MISO-Pad24)") (class "Default")
      (node (ref "IC2") (pin "24") (pinfunction "PC7(HS)/_SPI__MISO_24") (pintype "passive"))
    )
    (net (code "53") (name "unconnected-(IC2-PD0(HS){slash}_TIM3_CH2_[TIM1_BKIN]_[CLK_CCO]-Pad25)") (class "Default")
      (node (ref "IC2") (pin "25") (pinfunction "PD0(HS)/_TIM3_CH2_[TIM1_BKIN]_[CLK_CCO]_25") (pintype "passive"))
    )
    (net (code "54") (name "unconnected-(IC2-PD2(HS){slash}TIM3_CH1_[TIM2_CH3]-Pad27)") (class "Default")
      (node (ref "IC2") (pin "27") (pinfunction "PD2(HS)/TIM3_CH1_[TIM2_CH3]_27") (pintype "passive"))
    )
    (net (code "55") (name "unconnected-(IC2-[TIM1_CH1N]AIN0{slash}PB0-Pad16)") (class "Default")
      (node (ref "IC2") (pin "16") (pinfunction "[TIM1_CH1N]AIN0/PB0_16") (pintype "passive"))
    )
    (net (code "56") (name "unconnected-(IC2-[TIM1_CH2N]AIN1{slash}PB1-Pad15)") (class "Default")
      (node (ref "IC2") (pin "15") (pinfunction "[TIM1_CH2N]AIN1/PB1_15") (pintype "passive"))
    )
    (net (code "57") (name "unconnected-(IC2-[TIM1_CH3N]AIN2{slash}PB2-Pad14)") (class "Default")
      (node (ref "IC2") (pin "14") (pinfunction "[TIM1_CH3N]AIN2/PB2_14") (pintype "passive"))
    )
    (net (code "58") (name "unconnected-(IC3-CRFILT-Pad14)") (class "Default")
      (node (ref "IC3") (pin "14") (pinfunction "CRFILT_14") (pintype "passive+no_connect"))
    )
    (net (code "59") (name "unconnected-(IC3-OCS_N2-Pad17)") (class "Default")
      (node (ref "IC3") (pin "17") (pinfunction "OCS_N2_17") (pintype "passive"))
    )
    (net (code "60") (name "unconnected-(IC3-OCS_N3-Pad19)") (class "Default")
      (node (ref "IC3") (pin "19") (pinfunction "OCS_N3_19") (pintype "passive"))
    )
    (net (code "61") (name "unconnected-(IC3-OCS_N4-Pad21)") (class "Default")
      (node (ref "IC3") (pin "21") (pinfunction "OCS_N4_21") (pintype "passive"))
    )
    (net (code "62") (name "unconnected-(IC3-PRTPWR1{slash}BC_EN1-Pad12)") (class "Default")
      (node (ref "IC3") (pin "12") (pinfunction "PRTPWR1/BC_EN1_12") (pintype "passive+no_connect"))
    )
    (net (code "63") (name "unconnected-(IC3-PRTPWR2{slash}BC_EN2-Pad16)") (class "Default")
      (node (ref "IC3") (pin "16") (pinfunction "PRTPWR2/BC_EN2_16") (pintype "passive+no_connect"))
    )
    (net (code "64") (name "unconnected-(IC3-PRTPWR3{slash}BC_EN3-Pad18)") (class "Default")
      (node (ref "IC3") (pin "18") (pinfunction "PRTPWR3/BC_EN3_18") (pintype "passive+no_connect"))
    )
    (net (code "65") (name "unconnected-(IC3-PRTPWR4{slash}BC_EN4-Pad20)") (class "Default")
      (node (ref "IC3") (pin "20") (pinfunction "PRTPWR4/BC_EN4_20") (pintype "passive+no_connect"))
    )
    (net (code "66") (name "unconnected-(IC3-SUSP_IND{slash}LOCAL_PWR{slash}NON_REM0-Pad28)") (class "Default")
      (node (ref "IC3") (pin "28") (pinfunction "SUSP_IND/LOCAL_PWR/NON_REM0_28") (pintype "passive"))
    )
  )
)
